# Sheet1.net
KiCad netlist of a schematic drawn in Altium Designer
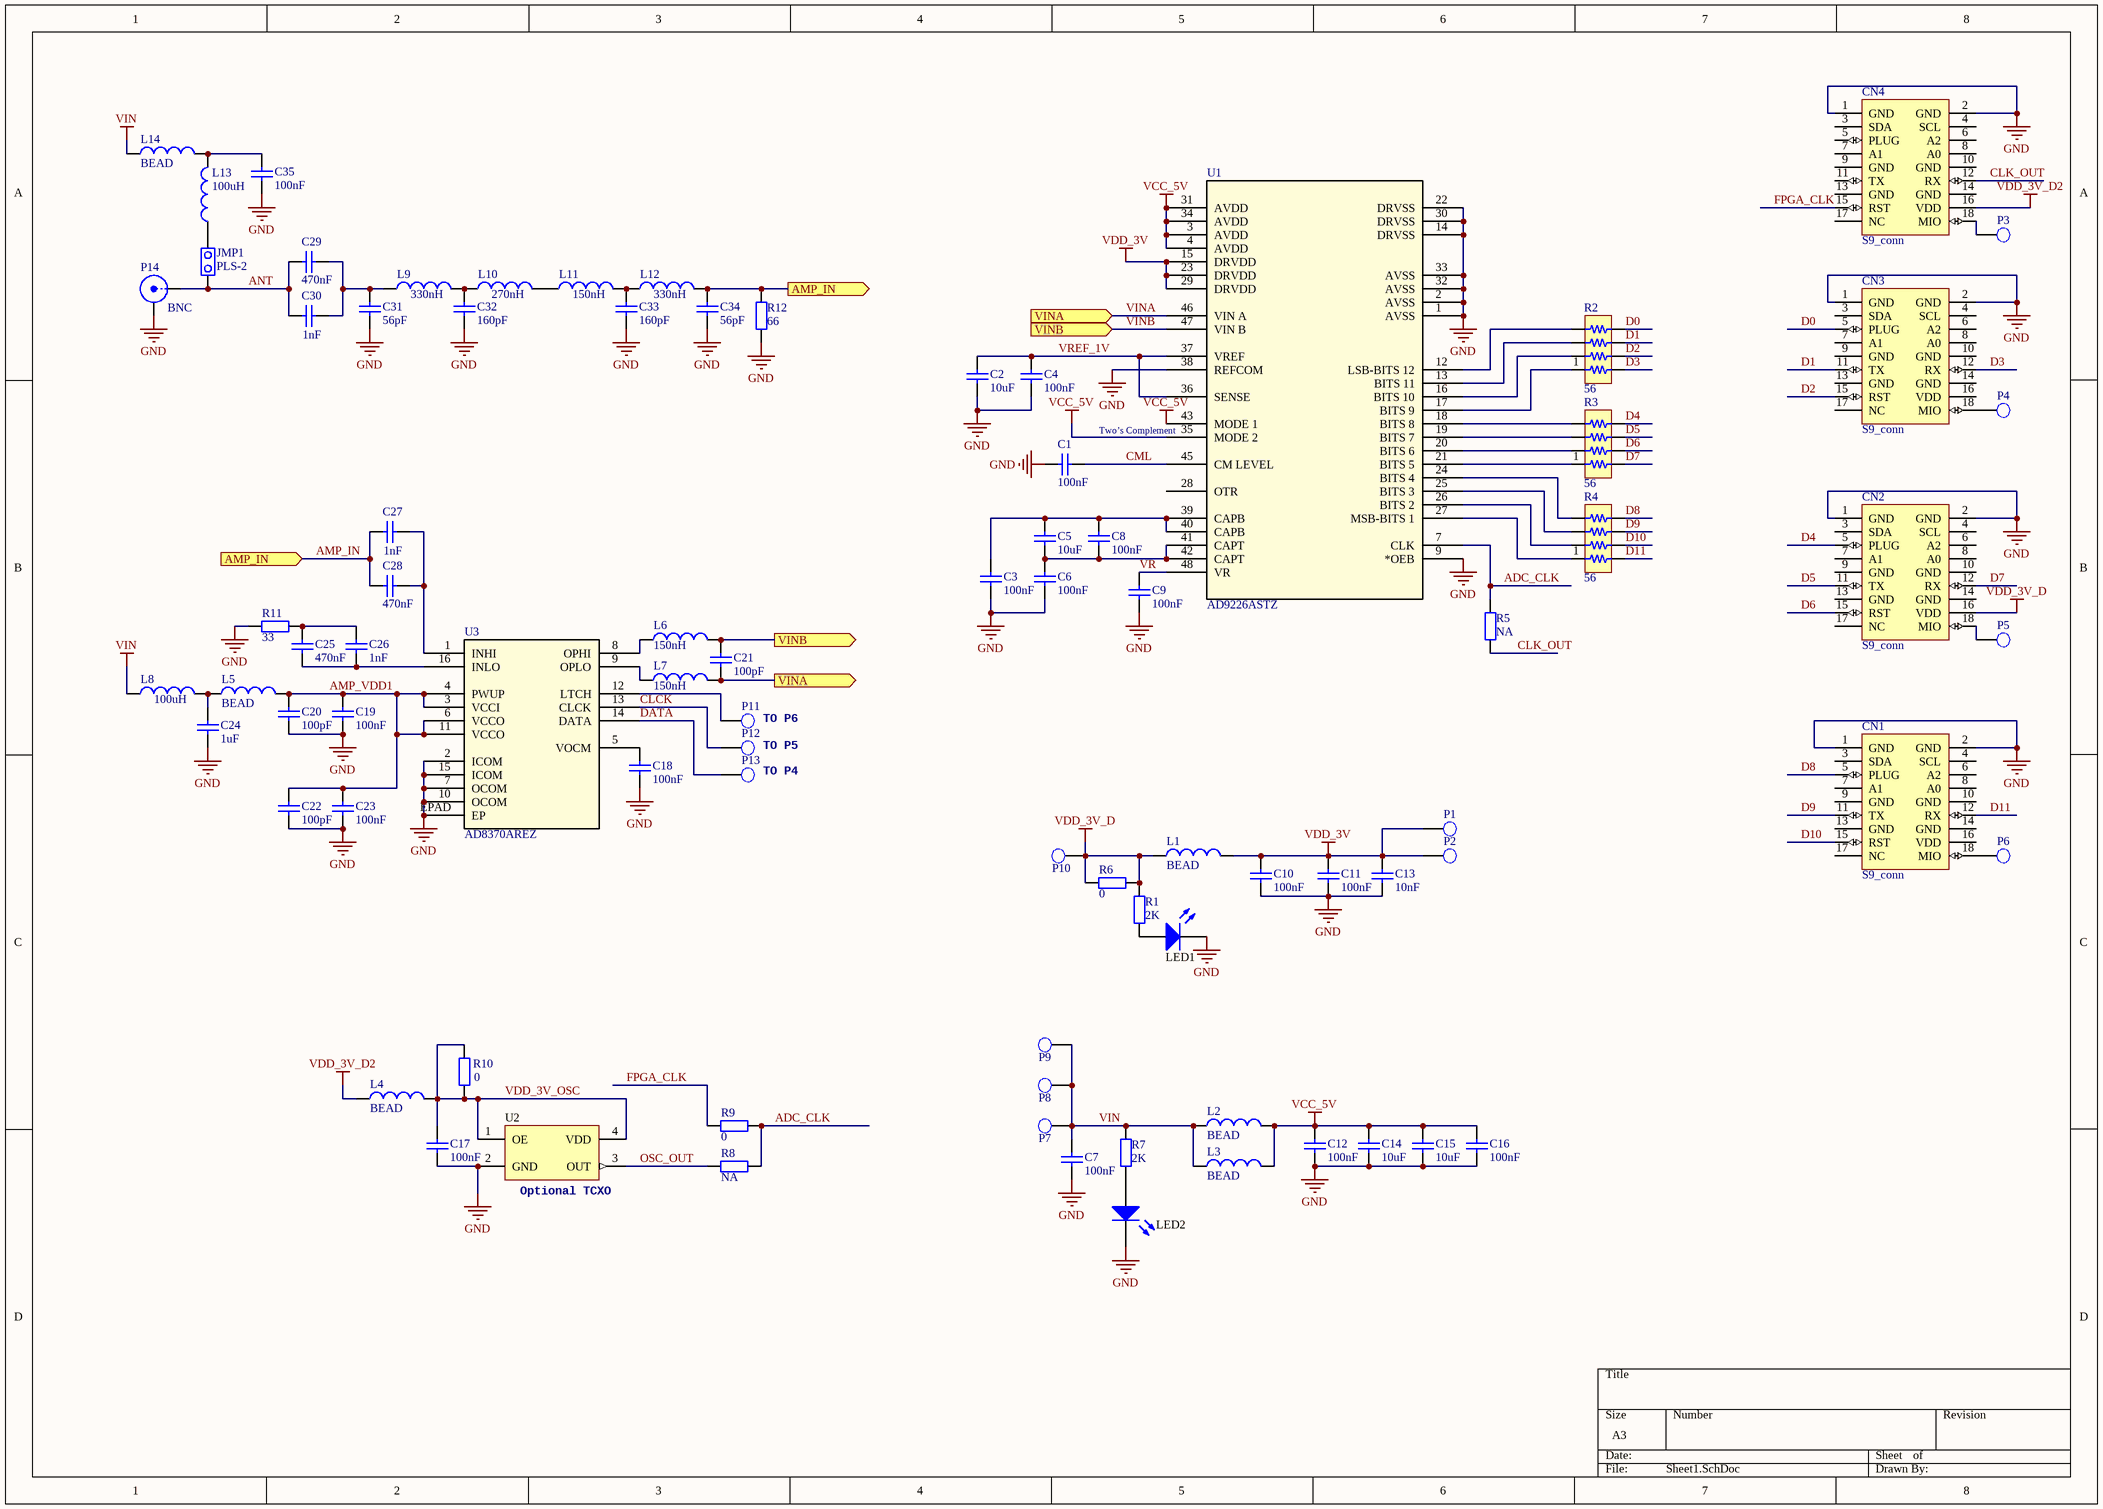
[diagram p0: Sheet1.SchDoc]

(export (version "E")
  (design (tool "Eeschema 10.0.6"))
  (components
    (comp (ref "C1")
      (value "100nF")
      (footprint "CAPC1608X90N")
      (description "Chip capacitor")
      (fields (field (name "VOLTAGE") "25V"))
      (libsource (lib "MyLibSch") (part "CC0805"))
    )
    (comp (ref "C2")
      (value "10uF")
      (footprint "CAPC1608X90N")
      (description "Chip capacitor")
      (fields (field (name "VOLTAGE") "25V"))
      (libsource (lib "MyLibSch") (part "CC0805"))
    )
    (comp (ref "C3")
      (value "100nF")
      (footprint "CAPC1608X90N")
      (description "Chip capacitor")
      (fields (field (name "VOLTAGE") "25V"))
      (libsource (lib "MyLibSch") (part "CC0805"))
    )
    (comp (ref "C4")
      (value "100nF")
      (footprint "CAPC1608X90N")
      (description "Chip capacitor")
      (fields (field (name "VOLTAGE") "25V"))
      (libsource (lib "MyLibSch") (part "CC0805"))
    )
    (comp (ref "C5")
      (value "10uF")
      (footprint "CAPC1608X90N")
      (description "Chip capacitor")
      (fields (field (name "VOLTAGE") "25V"))
      (libsource (lib "MyLibSch") (part "CC0805"))
    )
    (comp (ref "C6")
      (value "100nF")
      (footprint "CAPC1608X90N")
      (description "Chip capacitor")
      (fields (field (name "VOLTAGE") "25V"))
      (libsource (lib "MyLibSch") (part "CC0805"))
    )
    (comp (ref "C7")
      (value "100nF")
      (footprint "CAPC1608X90N")
      (description "Chip capacitor")
      (fields (field (name "VOLTAGE") "25V"))
      (libsource (lib "MyLibSch") (part "CC0805"))
    )
    (comp (ref "C8")
      (value "100nF")
      (footprint "CAPC1608X90N")
      (description "Chip capacitor")
      (fields (field (name "VOLTAGE") "25V"))
      (libsource (lib "MyLibSch") (part "CC0805"))
    )
    (comp (ref "C9")
      (value "100nF")
      (footprint "CAPC1608X90N")
      (description "Chip capacitor")
      (fields (field (name "VOLTAGE") "25V"))
      (libsource (lib "MyLibSch") (part "CC0805"))
    )
    (comp (ref "C10")
      (value "100nF")
      (footprint "CAPC1608X90N")
      (description "Chip capacitor")
      (fields (field (name "VOLTAGE") "25V"))
      (libsource (lib "MyLibSch") (part "CC0805"))
    )
    (comp (ref "C11")
      (value "100nF")
      (footprint "CAPC1608X90N")
      (description "Chip capacitor")
      (fields (field (name "VOLTAGE") "25V"))
      (libsource (lib "MyLibSch") (part "CC0805"))
    )
    (comp (ref "C12")
      (value "100nF")
      (footprint "CAPC1608X90N")
      (description "Chip capacitor")
      (fields (field (name "VOLTAGE") "25V"))
      (libsource (lib "MyLibSch") (part "CC0805"))
    )
    (comp (ref "C13")
      (value "10nF")
      (footprint "CAPC1608X90N")
      (description "Chip capacitor")
      (fields (field (name "VOLTAGE") "25V"))
      (libsource (lib "MyLibSch") (part "CC0805"))
    )
    (comp (ref "C14")
      (value "10uF")
      (footprint "CAPC1608X90N")
      (description "Chip capacitor")
      (fields (field (name "VOLTAGE") "25V"))
      (libsource (lib "MyLibSch") (part "CC0805"))
    )
    (comp (ref "C15")
      (value "10uF")
      (footprint "CAPC1608X90N")
      (description "Chip capacitor")
      (fields (field (name "VOLTAGE") "25V"))
      (libsource (lib "MyLibSch") (part "CC0805"))
    )
    (comp (ref "C16")
      (value "100nF")
      (footprint "CAPC1608X90N")
      (description "Chip capacitor")
      (fields (field (name "VOLTAGE") "25V"))
      (libsource (lib "MyLibSch") (part "CC0805"))
    )
    (comp (ref "C17")
      (value "100nF")
      (footprint "CAPC1608X90N")
      (description "Chip capacitor")
      (fields (field (name "VOLTAGE") "25V"))
      (libsource (lib "MyLibSch") (part "CC0805"))
    )
    (comp (ref "C18")
      (value "100nF")
      (footprint "CAPC2012X135N")
      (description "Chip capacitor")
      (fields (field (name "VOLTAGE") "25V"))
      (libsource (lib "MyLibSch") (part "CC0805"))
    )
    (comp (ref "C19")
      (value "100nF")
      (footprint "CAPC1608X90N")
      (description "Chip capacitor")
      (fields (field (name "VOLTAGE") "25V"))
      (libsource (lib "MyLibSch") (part "CC0805"))
    )
    (comp (ref "C20")
      (value "100pF")
      (footprint "CAPC1608X90N")
      (description "Chip capacitor")
      (fields (field (name "VOLTAGE") "25V"))
      (libsource (lib "MyLibSch") (part "CC0805"))
    )
    (comp (ref "C21")
      (value "100pF")
      (footprint "CAPC1608X90N")
      (description "Chip capacitor")
      (fields (field (name "VOLTAGE") "25V"))
      (libsource (lib "MyLibSch") (part "CC0805"))
    )
    (comp (ref "C22")
      (value "100pF")
      (footprint "CAPC1608X90N")
      (description "Chip capacitor")
      (fields (field (name "VOLTAGE") "25V"))
      (libsource (lib "MyLibSch") (part "CC0805"))
    )
    (comp (ref "C23")
      (value "100nF")
      (footprint "CAPC1608X90N")
      (description "Chip capacitor")
      (fields (field (name "VOLTAGE") "25V"))
      (libsource (lib "MyLibSch") (part "CC0805"))
    )
    (comp (ref "C24")
      (value "1uF")
      (footprint "CAPC1608X90N")
      (description "Chip capacitor")
      (fields (field (name "VOLTAGE") "25V"))
      (libsource (lib "MyLibSch") (part "CC0805"))
    )
    (comp (ref "C25")
      (value "470nF")
      (footprint "CAPC1608X90N")
      (description "Chip capacitor")
      (fields (field (name "VOLTAGE") "25V"))
      (libsource (lib "MyLibSch") (part "CC0805"))
    )
    (comp (ref "C26")
      (value "1nF")
      (footprint "CAPC1608X90N")
      (description "Chip capacitor")
      (fields (field (name "VOLTAGE") "25V"))
      (libsource (lib "MyLibSch") (part "CC0805"))
    )
    (comp (ref "C27")
      (value "1nF")
      (footprint "CAPC1608X90N")
      (description "Chip capacitor")
      (fields (field (name "VOLTAGE") "25V"))
      (libsource (lib "MyLibSch") (part "CC0805"))
    )
    (comp (ref "C28")
      (value "470nF")
      (footprint "CAPC1608X90N")
      (description "Chip capacitor")
      (fields (field (name "VOLTAGE") "25V"))
      (libsource (lib "MyLibSch") (part "CC0805"))
    )
    (comp (ref "C29")
      (value "470nF")
      (footprint "CAPC1608X90N")
      (description "Chip capacitor")
      (fields (field (name "VOLTAGE") "25V"))
      (libsource (lib "MyLibSch") (part "CC0805"))
    )
    (comp (ref "C30")
      (value "1nF")
      (footprint "CAPC1608X90N")
      (description "Chip capacitor")
      (fields (field (name "VOLTAGE") "25V"))
      (libsource (lib "MyLibSch") (part "CC0805"))
    )
    (comp (ref "C31")
      (value "56pF")
      (footprint "CAPC1608X90N")
      (description "Chip capacitor")
      (fields (field (name "VOLTAGE") "25V"))
      (libsource (lib "MyLibSch") (part "CC0805"))
    )
    (comp (ref "C32")
      (value "160pF")
      (footprint "CAPC1608X90N")
      (description "Chip capacitor")
      (fields (field (name "VOLTAGE") "25V"))
      (libsource (lib "MyLibSch") (part "CC0805"))
    )
    (comp (ref "C33")
      (value "160pF")
      (footprint "CAPC1608X90N")
      (description "Chip capacitor")
      (fields (field (name "VOLTAGE") "25V"))
      (libsource (lib "MyLibSch") (part "CC0805"))
    )
    (comp (ref "C34")
      (value "56pF")
      (footprint "CAPC1608X90N")
      (description "Chip capacitor")
      (fields (field (name "VOLTAGE") "25V"))
      (libsource (lib "MyLibSch") (part "CC0805"))
    )
    (comp (ref "C35")
      (value "100nF")
      (footprint "CAPC1608X90N")
      (description "Chip capacitor")
      (fields (field (name "VOLTAGE") "25V"))
      (libsource (lib "MyLibSch") (part "CC0805"))
    )
    (comp (ref "CN1") (value "S9_conn") (footprint "CONN9_2") (libsource (lib "lcd_lib") (part "S9_conn")))
    (comp (ref "CN2") (value "S9_conn") (footprint "CONN9_2") (libsource (lib "lcd_lib") (part "S9_conn")))
    (comp (ref "CN3") (value "S9_conn") (footprint "CONN9_2") (libsource (lib "lcd_lib") (part "S9_conn")))
    (comp (ref "CN4") (value "S9_conn") (footprint "CONN9_2") (libsource (lib "lcd_lib") (part "S9_conn")))
    (comp (ref "JMP1")
      (value "PLS-2")
      (footprint "HDR_1x2")
      (description "Jumper")
      (libsource (lib "MyLibConnectors") (part "JMP2"))
    )
    (comp (ref "L1")
      (value "BEAD")
      (footprint "INDC1608N")
      (description "Ferrit Bead")
      (libsource (lib "MyLibSch") (part "BEAD"))
    )
    (comp (ref "L2")
      (value "BEAD")
      (footprint "INDC1608N")
      (description "Ferrit Bead")
      (libsource (lib "MyLibSch") (part "BEAD"))
    )
    (comp (ref "L3")
      (value "BEAD")
      (footprint "INDC1608N")
      (description "Ferrit Bead")
      (libsource (lib "MyLibSch") (part "BEAD"))
    )
    (comp (ref "L4")
      (value "BEAD")
      (footprint "INDC1608N")
      (description "Ferrit Bead")
      (libsource (lib "MyLibSch") (part "BEAD"))
    )
    (comp (ref "L5")
      (value "BEAD")
      (footprint "INDC1608N")
      (description "Ferrit Bead")
      (libsource (lib "MyLibSch") (part "BEAD"))
    )
    (comp (ref "L6")
      (value "150nH")
      (footprint "RESC2012X70N")
      (description "Inductor")
      (fields (field (name "PUBLISHER") "Altium Limited"))
      (libsource (lib "Miscellaneous Devices") (part "Inductor"))
    )
    (comp (ref "L7")
      (value "150nH")
      (footprint "RESC2012X70N")
      (description "Inductor")
      (fields (field (name "PUBLISHER") "Altium Limited"))
      (libsource (lib "Miscellaneous Devices") (part "Inductor"))
    )
    (comp (ref "L8")
      (value "100uH")
      (footprint "INDC3216")
      (description "Inductor")
      (fields (field (name "PUBLISHER") "Altium Limited"))
      (libsource (lib "Miscellaneous Devices") (part "Inductor"))
    )
    (comp (ref "L9")
      (value "330nH")
      (footprint "MyLibPcb:V0805HD")
      (description "Inductor")
      (fields (field (name "PUBLISHER") "Altium Limited"))
      (libsource (lib "Miscellaneous Devices") (part "Inductor"))
    )
    (comp (ref "L10")
      (value "270nH")
      (footprint "MyLibPcb:V0805HD")
      (description "Inductor")
      (fields (field (name "PUBLISHER") "Altium Limited"))
      (libsource (lib "Miscellaneous Devices") (part "Inductor"))
    )
    (comp (ref "L11")
      (value "150nH")
      (footprint "MyLibPcb:V0805HD")
      (description "Inductor")
      (fields (field (name "PUBLISHER") "Altium Limited"))
      (libsource (lib "Miscellaneous Devices") (part "Inductor"))
    )
    (comp (ref "L12")
      (value "330nH")
      (footprint "MyLibPcb:V0805HD")
      (description "Inductor")
      (fields (field (name "PUBLISHER") "Altium Limited"))
      (libsource (lib "Miscellaneous Devices") (part "Inductor"))
    )
    (comp (ref "L13")
      (value "100uH")
      (footprint "INDC3216")
      (description "Inductor")
      (fields (field (name "PUBLISHER") "Altium Limited"))
      (libsource (lib "Miscellaneous Devices") (part "Inductor"))
    )
    (comp (ref "L14")
      (value "BEAD")
      (footprint "INDC1608N")
      (description "Ferrit Bead")
      (libsource (lib "MyLibSch") (part "BEAD"))
    )
    (comp (ref "LED1")
      (value "LED")
      (footprint "PcbLib3:LED_0603")
      (description "LED_0603")
      (libsource (lib "lcd_lib") (part "LED_0603"))
    )
    (comp (ref "LED2")
      (value "LED")
      (footprint "PcbLib3:LED_0603")
      (description "LED_0603")
      (libsource (lib "lcd_lib") (part "LED_0603"))
    )
    (comp (ref "P1")
      (value "Pad")
      (footprint "PcbLib3:Ext_pad_small2")
      (description "Pad for wire")
      (libsource (lib "lcd_lib") (part "Ext Pad"))
    )
    (comp (ref "P2")
      (value "Pad")
      (footprint "PcbLib3:Ext_pad_small2")
      (description "Pad for wire")
      (libsource (lib "lcd_lib") (part "Ext Pad"))
    )
    (comp (ref "P3")
      (value "Pad")
      (footprint "PcbLib3:Ext_pad_2")
      (description "Pad for wire")
      (libsource (lib "lcd_lib") (part "Ext Pad"))
    )
    (comp (ref "P4")
      (value "Pad")
      (footprint "PcbLib3:Ext_pad_2")
      (description "Pad for wire")
      (libsource (lib "lcd_lib") (part "Ext Pad"))
    )
    (comp (ref "P5")
      (value "Pad")
      (footprint "PcbLib3:Ext_pad_2")
      (description "Pad for wire")
      (libsource (lib "lcd_lib") (part "Ext Pad"))
    )
    (comp (ref "P6")
      (value "Pad")
      (footprint "PcbLib3:Ext_pad_2")
      (description "Pad for wire")
      (libsource (lib "lcd_lib") (part "Ext Pad"))
    )
    (comp (ref "P7")
      (value "Pad")
      (footprint "PcbLib3:Ext_pad_2")
      (description "Pad for wire")
      (libsource (lib "lcd_lib") (part "Ext Pad"))
    )
    (comp (ref "P8")
      (value "Pad")
      (footprint "Ext_hole")
      (description "Pad for wire")
      (libsource (lib "lcd_lib") (part "Ext Pad"))
    )
    (comp (ref "P9")
      (value "Pad")
      (footprint "Ext_hole")
      (description "Pad for wire")
      (libsource (lib "lcd_lib") (part "Ext Pad"))
    )
    (comp (ref "P10")
      (value "Pad")
      (footprint "PcbLib3:Ext_pad_small2")
      (description "Pad for wire")
      (libsource (lib "lcd_lib") (part "Ext Pad"))
    )
    (comp (ref "P11")
      (value "Pad")
      (footprint "PcbLib3:Ext_pad_small2")
      (description "Pad for wire")
      (libsource (lib "lcd_lib") (part "Ext Pad"))
    )
    (comp (ref "P12")
      (value "Pad")
      (footprint "PcbLib3:Ext_pad_small2")
      (description "Pad for wire")
      (libsource (lib "lcd_lib") (part "Ext Pad"))
    )
    (comp (ref "P13")
      (value "Pad")
      (footprint "PcbLib3:Ext_pad_small2")
      (description "Pad for wire")
      (libsource (lib "lcd_lib") (part "Ext Pad"))
    )
    (comp (ref "P14")
      (value "BNC")
      (footprint "BNC_RA CON")
      (description "BNC Elbow Connector")
      (fields (field (name "PUBLISHER") "Altium Limited"))
      (libsource (lib "Miscellaneous Connectors") (part "BNC"))
    )
    (comp (ref "R1")
      (value "2K")
      (footprint "RESC1608X55N")
      (description "Chip resistor")
      (fields (field (name "TOLERANCE") "5%"))
      (libsource (lib "MyLibSch") (part "RC0805"))
    )
    (comp (ref "R2")
      (value "56")
      (footprint "RESCAXS50P160X320X70-8N")
      (description "SMT Resistor Array")
      (libsource (lib "lcd_lib") (part "res_array_inv"))
    )
    (comp (ref "R3")
      (value "56")
      (footprint "RESCAXS50P160X320X70-8N")
      (description "SMT Resistor Array")
      (libsource (lib "lcd_lib") (part "res_array_inv"))
    )
    (comp (ref "R4")
      (value "56")
      (footprint "RESCAXS50P160X320X70-8N")
      (description "SMT Resistor Array")
      (libsource (lib "lcd_lib") (part "res_array_inv"))
    )
    (comp (ref "R5")
      (value "NA")
      (footprint "RESC1608X55N")
      (description "Chip resistor")
      (fields (field (name "TOLERANCE") "5%"))
      (libsource (lib "MyLibSch") (part "RC0805"))
    )
    (comp (ref "R6")
      (value "0")
      (footprint "RESC3216N_ZERO")
      (description "Chip resistor")
      (fields (field (name "TOLERANCE") "5%"))
      (libsource (lib "") (part "RC0805_1"))
    )
    (comp (ref "R7")
      (value "2K")
      (footprint "RESC1608X55N")
      (description "Chip resistor")
      (fields (field (name "TOLERANCE") "5%"))
      (libsource (lib "") (part "RC0805_2"))
    )
    (comp (ref "R8")
      (value "NA")
      (footprint "RESC1608X55N")
      (description "Chip resistor")
      (fields (field (name "TOLERANCE") "5%"))
      (libsource (lib "") (part "RC0805_1"))
    )
    (comp (ref "R9")
      (value "0")
      (footprint "RESC1608X55N")
      (description "Chip resistor")
      (fields (field (name "TOLERANCE") "5%"))
      (libsource (lib "") (part "RC0805_1"))
    )
    (comp (ref "R10")
      (value "0")
      (footprint "RESC3216N_ZERO")
      (description "Chip resistor")
      (fields (field (name "TOLERANCE") "5%"))
      (libsource (lib "MyLibSch") (part "RC0805"))
    )
    (comp (ref "R11")
      (value "33")
      (footprint "RESC1608X55N")
      (description "Chip resistor")
      (fields (field (name "TOLERANCE") "5%"))
      (libsource (lib "") (part "RC0805_1"))
    )
    (comp (ref "R12")
      (value "66")
      (footprint "RESC1608X55N")
      (description "Chip resistor")
      (fields (field (name "TOLERANCE") "5%"))
      (libsource (lib "MyLibSch") (part "RC0805"))
    )
    (comp (ref "U1")
      (value "AD9226ASTZ")
      (footprint "ST_48_ADI")
      (description "No Description Available")
      (libsource (lib "AD9226ASTZ") (part "AD9226ASTZ"))
    )
    (comp (ref "U2")
      (value "40MHz")
      (footprint "SX-6 QUARTZ")
      (description "Quartz Osc")
      (fields (field (name "Comment") "Quartz"))
      (libsource (lib "lcd_lib") (part "Quartz Osc"))
    )
    (comp (ref "U3")
      (value "AD8370AREZ")
      (footprint "RE_16_2_ADI")
      (description "No Description Available")
      (libsource (lib "AD8370AREZ") (part "AD8370AREZ"))
    )
  )
  (nets
    (net (code "1") (name "/ADC_CLK") (class "Default")
      (node (ref "R5") (pin "1") (pinfunction "1_1") (pintype "passive"))
      (node (ref "R8") (pin "1") (pinfunction "1_1") (pintype "passive"))
      (node (ref "R9") (pin "1") (pinfunction "1_1") (pintype "passive"))
      (node (ref "U1") (pin "7") (pinfunction "CLK_7") (pintype "passive"))
    )
    (net (code "2") (name "/AMP_IN") (class "Default")
      (node (ref "C27") (pin "2") (pinfunction "2_2") (pintype "passive"))
      (node (ref "C28") (pin "2") (pinfunction "2_2") (pintype "passive"))
      (node (ref "C34") (pin "2") (pinfunction "2_2") (pintype "passive"))
      (node (ref "L12") (pin "2") (pinfunction "2_2") (pintype "passive"))
      (node (ref "R12") (pin "1") (pinfunction "1_1") (pintype "passive"))
    )
    (net (code "3") (name "/AMP_VDD1") (class "Default")
      (node (ref "C19") (pin "2") (pinfunction "2_2") (pintype "passive"))
      (node (ref "C20") (pin "2") (pinfunction "2_2") (pintype "passive"))
      (node (ref "C22") (pin "2") (pinfunction "2_2") (pintype "passive"))
      (node (ref "C23") (pin "2") (pinfunction "2_2") (pintype "passive"))
      (node (ref "L5") (pin "2") (pinfunction "2_2") (pintype "passive"))
      (node (ref "U3") (pin "11") (pinfunction "VCCO_11") (pintype "power_in"))
      (node (ref "U3") (pin "3") (pinfunction "VCCI_3") (pintype "power_in"))
      (node (ref "U3") (pin "4") (pinfunction "PWUP_4") (pintype "passive"))
      (node (ref "U3") (pin "6") (pinfunction "VCCO_6") (pintype "power_in"))
    )
    (net (code "4") (name "/ANT") (class "Default")
      (node (ref "C29") (pin "2") (pinfunction "2_2") (pintype "passive"))
      (node (ref "C30") (pin "2") (pinfunction "2_2") (pintype "passive"))
      (node (ref "JMP1") (pin "1") (pinfunction "1_1") (pintype "passive"))
      (node (ref "P14") (pin "1") (pinfunction "X_1") (pintype "passive"))
    )
    (net (code "5") (name "/CLCK") (class "Default")
      (node (ref "P12") (pin "1") (pinfunction "Pad_1") (pintype "passive"))
      (node (ref "U3") (pin "13") (pinfunction "CLCK_13") (pintype "passive"))
    )
    (net (code "6") (name "/CLK_OUT") (class "Default")
      (node (ref "CN4") (pin "12") (pinfunction "RX_12") (pintype "bidirectional"))
      (node (ref "R5") (pin "2") (pinfunction "2_2") (pintype "passive"))
    )
    (net (code "7") (name "/CML") (class "Default")
      (node (ref "C1") (pin "2") (pinfunction "2_2") (pintype "passive"))
      (node (ref "U1") (pin "45") (pinfunction "CM_LEVEL_45") (pintype "passive"))
    )
    (net (code "8") (name "/D0") (class "Default")
      (node (ref "CN3") (pin "5") (pinfunction "PLUG_5") (pintype "bidirectional"))
      (node (ref "R2") (pin "5") (pinfunction "5_5") (pintype "passive"))
    )
    (net (code "9") (name "/D1") (class "Default")
      (node (ref "CN3") (pin "11") (pinfunction "TX_11") (pintype "bidirectional"))
      (node (ref "R2") (pin "6") (pinfunction "6_6") (pintype "passive"))
    )
    (net (code "10") (name "/D2") (class "Default")
      (node (ref "CN3") (pin "15") (pinfunction "RST_15") (pintype "bidirectional"))
      (node (ref "R2") (pin "7") (pinfunction "7_7") (pintype "passive"))
    )
    (net (code "11") (name "/D3") (class "Default")
      (node (ref "CN3") (pin "12") (pinfunction "RX_12") (pintype "bidirectional"))
      (node (ref "R2") (pin "8") (pinfunction "8_8") (pintype "passive"))
    )
    (net (code "12") (name "/D4") (class "Default")
      (node (ref "CN2") (pin "5") (pinfunction "PLUG_5") (pintype "bidirectional"))
      (node (ref "R3") (pin "5") (pinfunction "5_5") (pintype "passive"))
    )
    (net (code "13") (name "/D5") (class "Default")
      (node (ref "CN2") (pin "11") (pinfunction "TX_11") (pintype "bidirectional"))
      (node (ref "R3") (pin "6") (pinfunction "6_6") (pintype "passive"))
    )
    (net (code "14") (name "/D6") (class "Default")
      (node (ref "CN2") (pin "15") (pinfunction "RST_15") (pintype "bidirectional"))
      (node (ref "R3") (pin "7") (pinfunction "7_7") (pintype "passive"))
    )
    (net (code "15") (name "/D7") (class "Default")
      (node (ref "CN2") (pin "12") (pinfunction "RX_12") (pintype "bidirectional"))
      (node (ref "R3") (pin "8") (pinfunction "8_8") (pintype "passive"))
    )
    (net (code "16") (name "/D8") (class "Default")
      (node (ref "CN1") (pin "5") (pinfunction "PLUG_5") (pintype "bidirectional"))
      (node (ref "R4") (pin "5") (pinfunction "5_5") (pintype "passive"))
    )
    (net (code "17") (name "/D9") (class "Default")
      (node (ref "CN1") (pin "11") (pinfunction "TX_11") (pintype "bidirectional"))
      (node (ref "R4") (pin "6") (pinfunction "6_6") (pintype "passive"))
    )
    (net (code "18") (name "/D10") (class "Default")
      (node (ref "CN1") (pin "15") (pinfunction "RST_15") (pintype "bidirectional"))
      (node (ref "R4") (pin "7") (pinfunction "7_7") (pintype "passive"))
    )
    (net (code "19") (name "/D11") (class "Default")
      (node (ref "CN1") (pin "12") (pinfunction "RX_12") (pintype "bidirectional"))
      (node (ref "R4") (pin "8") (pinfunction "8_8") (pintype "passive"))
    )
    (net (code "20") (name "/DATA") (class "Default")
      (node (ref "P13") (pin "1") (pinfunction "Pad_1") (pintype "passive"))
      (node (ref "U3") (pin "14") (pinfunction "DATA_14") (pintype "passive"))
    )
    (net (code "21") (name "/FPGA_CLK") (class "Default")
      (node (ref "CN4") (pin "15") (pinfunction "RST_15") (pintype "bidirectional"))
      (node (ref "R9") (pin "2") (pinfunction "2_2") (pintype "passive"))
    )
    (net (code "22") (name "/OSC_OUT") (class "Default")
      (node (ref "R8") (pin "2") (pinfunction "2_2") (pintype "passive"))
      (node (ref "U2") (pin "3") (pinfunction "OUT_3") (pintype "output"))
    )
    (net (code "23") (name "/VDD_3V_OSC") (class "Default")
      (node (ref "C17") (pin "2") (pinfunction "2_2") (pintype "passive"))
      (node (ref "L4") (pin "2") (pinfunction "2_2") (pintype "passive"))
      (node (ref "R10") (pin "1") (pinfunction "1_1") (pintype "passive"))
      (node (ref "R10") (pin "2") (pinfunction "2_2") (pintype "passive"))
      (node (ref "U2") (pin "1") (pinfunction "OE_1") (pintype "passive"))
      (node (ref "U2") (pin "4") (pinfunction "VDD_4") (pintype "power_in"))
    )
    (net (code "24") (name "/VINA") (class "Default")
      (node (ref "C21") (pin "1") (pinfunction "1_1") (pintype "passive"))
      (node (ref "L7") (pin "2") (pinfunction "2_2") (pintype "passive"))
      (node (ref "U1") (pin "46") (pinfunction "VIN_A_46") (pintype "passive"))
    )
    (net (code "25") (name "/VINB") (class "Default")
      (node (ref "C21") (pin "2") (pinfunction "2_2") (pintype "passive"))
      (node (ref "L6") (pin "2") (pinfunction "2_2") (pintype "passive"))
      (node (ref "U1") (pin "47") (pinfunction "VIN_B_47") (pintype "passive"))
    )
    (net (code "26") (name "/VR") (class "Default")
      (node (ref "C9") (pin "2") (pinfunction "2_2") (pintype "passive"))
      (node (ref "U1") (pin "48") (pinfunction "VR_48") (pintype "passive"))
    )
    (net (code "27") (name "/VREF_1V") (class "Default")
      (node (ref "C2") (pin "2") (pinfunction "2_2") (pintype "passive"))
      (node (ref "C4") (pin "2") (pinfunction "2_2") (pintype "passive"))
      (node (ref "U1") (pin "36") (pinfunction "SENSE_36") (pintype "passive"))
      (node (ref "U1") (pin "37") (pinfunction "VREF_37") (pintype "passive"))
    )
    (net (code "28") (name "GND") (class "Default")
      (node (ref "C1") (pin "1") (pinfunction "1_1") (pintype "passive"))
      (node (ref "C10") (pin "1") (pinfunction "1_1") (pintype "passive"))
      (node (ref "C11") (pin "1") (pinfunction "1_1") (pintype "passive"))
      (node (ref "C12") (pin "1") (pinfunction "1_1") (pintype "passive"))
      (node (ref "C13") (pin "1") (pinfunction "1_1") (pintype "passive"))
      (node (ref "C14") (pin "1") (pinfunction "1_1") (pintype "passive"))
      (node (ref "C15") (pin "1") (pinfunction "1_1") (pintype "passive"))
      (node (ref "C16") (pin "1") (pinfunction "1_1") (pintype "passive"))
      (node (ref "C17") (pin "1") (pinfunction "1_1") (pintype "passive"))
      (node (ref "C18") (pin "1") (pinfunction "1_1") (pintype "passive"))
      (node (ref "C19") (pin "1") (pinfunction "1_1") (pintype "passive"))
      (node (ref "C2") (pin "1") (pinfunction "1_1") (pintype "passive"))
      (node (ref "C20") (pin "1") (pinfunction "1_1") (pintype "passive"))
      (node (ref "C22") (pin "1") (pinfunction "1_1") (pintype "passive"))
      (node (ref "C23") (pin "1") (pinfunction "1_1") (pintype "passive"))
      (node (ref "C24") (pin "1") (pinfunction "1_1") (pintype "passive"))
      (node (ref "C3") (pin "1") (pinfunction "1_1") (pintype "passive"))
      (node (ref "C31") (pin "1") (pinfunction "1_1") (pintype "passive"))
      (node (ref "C32") (pin "1") (pinfunction "1_1") (pintype "passive"))
      (node (ref "C33") (pin "1") (pinfunction "1_1") (pintype "passive"))
      (node (ref "C34") (pin "1") (pinfunction "1_1") (pintype "passive"))
      (node (ref "C35") (pin "1") (pinfunction "1_1") (pintype "passive"))
      (node (ref "C4") (pin "1") (pinfunction "1_1") (pintype "passive"))
      (node (ref "C6") (pin "1") (pinfunction "1_1") (pintype "passive"))
      (node (ref "C7") (pin "1") (pinfunction "1_1") (pintype "passive"))
      (node (ref "C9") (pin "1") (pinfunction "1_1") (pintype "passive"))
      (node (ref "CN1") (pin "1") (pinfunction "GND_1") (pintype "passive"))
      (node (ref "CN1") (pin "2") (pinfunction "GND_2") (pintype "passive"))
      (node (ref "CN2") (pin "1") (pinfunction "GND_1") (pintype "passive"))
      (node (ref "CN2") (pin "2") (pinfunction "GND_2") (pintype "passive"))
      (node (ref "CN3") (pin "1") (pinfunction "GND_1") (pintype "passive"))
      (node (ref "CN3") (pin "2") (pinfunction "GND_2") (pintype "passive"))
      (node (ref "CN4") (pin "1") (pinfunction "GND_1") (pintype "passive"))
      (node (ref "CN4") (pin "2") (pinfunction "GND_2") (pintype "passive"))
      (node (ref "LED1") (pin "2") (pinfunction "K_2") (pintype "passive"))
      (node (ref "LED2") (pin "2") (pinfunction "K_2") (pintype "passive"))
      (node (ref "P14") (pin "2") (pinfunction "Y_2") (pintype "passive"))
      (node (ref "R11") (pin "2") (pinfunction "2_2") (pintype "passive"))
      (node (ref "R12") (pin "2") (pinfunction "2_2") (pintype "passive"))
      (node (ref "U1") (pin "1") (pinfunction "AVSS_1") (pintype "passive"))
      (node (ref "U1") (pin "14") (pinfunction "DRVSS_14") (pintype "passive"))
      (node (ref "U1") (pin "2") (pinfunction "AVSS_2") (pintype "passive"))
      (node (ref "U1") (pin "22") (pinfunction "DRVSS_22") (pintype "passive"))
      (node (ref "U1") (pin "30") (pinfunction "DRVSS_30") (pintype "passive"))
      (node (ref "U1") (pin "32") (pinfunction "AVSS_32") (pintype "passive"))
      (node (ref "U1") (pin "33") (pinfunction "AVSS_33") (pintype "passive"))
      (node (ref "U1") (pin "38") (pinfunction "REFCOM_38") (pintype "passive"))
      (node (ref "U1") (pin "9") (pinfunction "*OEB_9") (pintype "passive"))
      (node (ref "U2") (pin "2") (pinfunction "GND_2") (pintype "power_in"))
      (node (ref "U3") (pin "10") (pinfunction "OCOM_10") (pintype "passive"))
      (node (ref "U3") (pin "15") (pinfunction "ICOM_15") (pintype "passive"))
      (node (ref "U3") (pin "2") (pinfunction "ICOM_2") (pintype "passive"))
      (node (ref "U3") (pin "7") (pinfunction "OCOM_7") (pintype "passive"))
      (node (ref "U3") (pin "EPAD") (pinfunction "EP_EPAD") (pintype "passive"))
    )
    (net (code "29") (name "Net-(C3-Pad2)") (class "Default")
      (node (ref "C3") (pin "2") (pinfunction "2_2") (pintype "passive"))
      (node (ref "C5") (pin "2") (pinfunction "2_2") (pintype "passive"))
      (node (ref "C8") (pin "2") (pinfunction "2_2") (pintype "passive"))
      (node (ref "U1") (pin "39") (pinfunction "CAPB_39") (pintype "passive"))
      (node (ref "U1") (pin "40") (pinfunction "CAPB_40") (pintype "passive"))
    )
    (net (code "30") (name "Net-(C5-Pad1)") (class "Default")
      (node (ref "C5") (pin "1") (pinfunction "1_1") (pintype "passive"))
      (node (ref "C6") (pin "2") (pinfunction "2_2") (pintype "passive"))
      (node (ref "C8") (pin "1") (pinfunction "1_1") (pintype "passive"))
      (node (ref "U1") (pin "41") (pinfunction "CAPT_41") (pintype "passive"))
      (node (ref "U1") (pin "42") (pinfunction "CAPT_42") (pintype "passive"))
    )
    (net (code "31") (name "Net-(C24-Pad2)") (class "Default")
      (node (ref "C24") (pin "2") (pinfunction "2_2") (pintype "passive"))
      (node (ref "L5") (pin "1") (pinfunction "1_1") (pintype "passive"))
      (node (ref "L8") (pin "2") (pinfunction "2_2") (pintype "passive"))
    )
    (net (code "32") (name "Net-(C25-Pad2)") (class "Default")
      (node (ref "C25") (pin "2") (pinfunction "2_2") (pintype "passive"))
      (node (ref "C26") (pin "2") (pinfunction "2_2") (pintype "passive"))
      (node (ref "R11") (pin "1") (pinfunction "1_1") (pintype "passive"))
    )
    (net (code "33") (name "Net-(C29-Pad1)") (class "Default")
      (node (ref "C29") (pin "1") (pinfunction "1_1") (pintype "passive"))
      (node (ref "C30") (pin "1") (pinfunction "1_1") (pintype "passive"))
      (node (ref "C31") (pin "2") (pinfunction "2_2") (pintype "passive"))
      (node (ref "L9") (pin "1") (pinfunction "1_1") (pintype "passive"))
    )
    (net (code "34") (name "Net-(C32-Pad2)") (class "Default")
      (node (ref "C32") (pin "2") (pinfunction "2_2") (pintype "passive"))
      (node (ref "L10") (pin "1") (pinfunction "1_1") (pintype "passive"))
      (node (ref "L9") (pin "2") (pinfunction "2_2") (pintype "passive"))
    )
    (net (code "35") (name "Net-(C33-Pad2)") (class "Default")
      (node (ref "C33") (pin "2") (pinfunction "2_2") (pintype "passive"))
      (node (ref "L11") (pin "2") (pinfunction "2_2") (pintype "passive"))
      (node (ref "L12") (pin "1") (pinfunction "1_1") (pintype "passive"))
    )
    (net (code "36") (name "Net-(C35-Pad2)") (class "Default")
      (node (ref "C35") (pin "2") (pinfunction "2_2") (pintype "passive"))
      (node (ref "L13") (pin "2") (pinfunction "2_2") (pintype "passive"))
      (node (ref "L14") (pin "2") (pinfunction "2_2") (pintype "passive"))
    )
    (net (code "37") (name "Net-(CN1-MIO)") (class "Default")
      (node (ref "CN1") (pin "18") (pinfunction "MIO_18") (pintype "bidirectional"))
      (node (ref "P6") (pin "1") (pinfunction "Pad_1") (pintype "passive"))
    )
    (net (code "38") (name "Net-(CN2-MIO)") (class "Default")
      (node (ref "CN2") (pin "18") (pinfunction "MIO_18") (pintype "bidirectional"))
      (node (ref "P5") (pin "1") (pinfunction "Pad_1") (pintype "passive"))
    )
    (net (code "39") (name "Net-(CN3-MIO)") (class "Default")
      (node (ref "CN3") (pin "18") (pinfunction "MIO_18") (pintype "bidirectional"))
      (node (ref "P4") (pin "1") (pinfunction "Pad_1") (pintype "passive"))
    )
    (net (code "40") (name "Net-(CN4-MIO)") (class "Default")
      (node (ref "CN4") (pin "18") (pinfunction "MIO_18") (pintype "bidirectional"))
      (node (ref "P3") (pin "1") (pinfunction "Pad_1") (pintype "passive"))
    )
    (net (code "41") (name "Net-(JMP1-Pad2)") (class "Default")
      (node (ref "JMP1") (pin "2") (pinfunction "2_2") (pintype "passive"))
      (node (ref "L13") (pin "1") (pinfunction "1_1") (pintype "passive"))
    )
    (net (code "42") (name "Net-(L10-Pad2)") (class "Default")
      (node (ref "L10") (pin "2") (pinfunction "2_2") (pintype "passive"))
      (node (ref "L11") (pin "1") (pinfunction "1_1") (pintype "passive"))
    )
    (net (code "43") (name "Net-(LED1-A)") (class "Default")
      (node (ref "LED1") (pin "1") (pinfunction "A_1") (pintype "passive"))
      (node (ref "R1") (pin "2") (pinfunction "2_2") (pintype "passive"))
    )
    (net (code "44") (name "Net-(LED2-A)") (class "Default")
      (node (ref "LED2") (pin "1") (pinfunction "A_1") (pintype "passive"))
      (node (ref "R7") (pin "1") (pinfunction "1_1") (pintype "passive"))
    )
    (net (code "45") (name "Net-(U1-BITS_2)") (class "Default")
      (node (ref "R4") (pin "2") (pinfunction "2_2") (pintype "passive"))
      (node (ref "U1") (pin "26") (pinfunction "BITS_2_26") (pintype "passive"))
    )
    (net (code "46") (name "Net-(U1-BITS_3)") (class "Default")
      (node (ref "R4") (pin "3") (pinfunction "3_3") (pintype "passive"))
      (node (ref "U1") (pin "25") (pinfunction "BITS_3_25") (pintype "passive"))
    )
    (net (code "47") (name "Net-(U1-BITS_4)") (class "Default")
      (node (ref "R4") (pin "4") (pinfunction "4_4") (pintype "passive"))
      (node (ref "U1") (pin "24") (pinfunction "BITS_4_24") (pintype "passive"))
    )
    (net (code "48") (name "Net-(U1-BITS_5)") (class "Default")
      (node (ref "R3") (pin "1") (pinfunction "1_1") (pintype "passive"))
      (node (ref "U1") (pin "21") (pinfunction "BITS_5_21") (pintype "passive"))
    )
    (net (code "49") (name "Net-(U1-BITS_6)") (class "Default")
      (node (ref "R3") (pin "2") (pinfunction "2_2") (pintype "passive"))
      (node (ref "U1") (pin "20") (pinfunction "BITS_6_20") (pintype "passive"))
    )
    (net (code "50") (name "Net-(U1-BITS_7)") (class "Default")
      (node (ref "R3") (pin "3") (pinfunction "3_3") (pintype "passive"))
      (node (ref "U1") (pin "19") (pinfunction "BITS_7_19") (pintype "passive"))
    )
    (net (code "51") (name "Net-(U1-BITS_8)") (class "Default")
      (node (ref "R3") (pin "4") (pinfunction "4_4") (pintype "passive"))
      (node (ref "U1") (pin "18") (pinfunction "BITS_8_18") (pintype "passive"))
    )
    (net (code "52") (name "Net-(U1-BITS_9)") (class "Default")
      (node (ref "R2") (pin "1") (pinfunction "1_1") (pintype "passive"))
      (node (ref "U1") (pin "17") (pinfunction "BITS_9_17") (pintype "passive"))
    )
    (net (code "53") (name "Net-(U1-BITS_10)") (class "Default")
      (node (ref "R2") (pin "2") (pinfunction "2_2") (pintype "passive"))
      (node (ref "U1") (pin "16") (pinfunction "BITS_10_16") (pintype "passive"))
    )
    (net (code "54") (name "Net-(U1-BITS_11)") (class "Default")
      (node (ref "R2") (pin "3") (pinfunction "3_3") (pintype "passive"))
      (node (ref "U1") (pin "13") (pinfunction "BITS_11_13") (pintype "passive"))
    )
    (net (code "55") (name "Net-(U1-LSB-BITS_12)") (class "Default")
      (node (ref "R2") (pin "4") (pinfunction "4_4") (pintype "passive"))
      (node (ref "U1") (pin "12") (pinfunction "LSB-BITS_12_12") (pintype "passive"))
    )
    (net (code "56") (name "Net-(U1-MSB-BITS_1)") (class "Default")
      (node (ref "R4") (pin "1") (pinfunction "1_1") (pintype "passive"))
      (node (ref "U1") (pin "27") (pinfunction "MSB-BITS_1_27") (pintype "passive"))
    )
    (net (code "57") (name "Net-(U3-INHI)") (class "Default")
      (node (ref "C27") (pin "1") (pinfunction "1_1") (pintype "passive"))
      (node (ref "C28") (pin "1") (pinfunction "1_1") (pintype "passive"))
      (node (ref "U3") (pin "1") (pinfunction "INHI_1") (pintype "passive"))
    )
    (net (code "58") (name "Net-(U3-INLO)") (class "Default")
      (node (ref "C25") (pin "1") (pinfunction "1_1") (pintype "passive"))
      (node (ref "C26") (pin "1") (pinfunction "1_1") (pintype "passive"))
      (node (ref "U3") (pin "16") (pinfunction "INLO_16") (pintype "passive"))
    )
    (net (code "59") (name "Net-(U3-LTCH)") (class "Default")
      (node (ref "P11") (pin "1") (pinfunction "Pad_1") (pintype "passive"))
      (node (ref "U3") (pin "12") (pinfunction "LTCH_12") (pintype "passive"))
    )
    (net (code "60") (name "Net-(U3-OPHI)") (class "Default")
      (node (ref "L6") (pin "1") (pinfunction "1_1") (pintype "passive"))
      (node (ref "U3") (pin "8") (pinfunction "OPHI_8") (pintype "passive"))
    )
    (net (code "61") (name "Net-(U3-OPLO)") (class "Default")
      (node (ref "L7") (pin "1") (pinfunction "1_1") (pintype "passive"))
      (node (ref "U3") (pin "9") (pinfunction "OPLO_9") (pintype "passive"))
    )
    (net (code "62") (name "Net-(U3-VOCM)") (class "Default")
      (node (ref "C18") (pin "2") (pinfunction "2_2") (pintype "passive"))
      (node (ref "U3") (pin "5") (pinfunction "VOCM_5") (pintype "passive"))
    )
    (net (code "63") (name "VCC_5V") (class "Default")
      (node (ref "C12") (pin "2") (pinfunction "2_2") (pintype "passive"))
      (node (ref "C14") (pin "2") (pinfunction "2_2") (pintype "passive"))
      (node (ref "C15") (pin "2") (pinfunction "2_2") (pintype "passive"))
      (node (ref "C16") (pin "2") (pinfunction "2_2") (pintype "passive"))
      (node (ref "L2") (pin "2") (pinfunction "2_2") (pintype "passive"))
      (node (ref "L3") (pin "2") (pinfunction "2_2") (pintype "passive"))
      (node (ref "U1") (pin "3") (pinfunction "AVDD_3") (pintype "passive"))
      (node (ref "U1") (pin "31") (pinfunction "AVDD_31") (pintype "passive"))
      (node (ref "U1") (pin "34") (pinfunction "AVDD_34") (pintype "passive"))
      (node (ref "U1") (pin "35") (pinfunction "MODE_2_35") (pintype "passive"))
      (node (ref "U1") (pin "4") (pinfunction "AVDD_4") (pintype "passive"))
      (node (ref "U1") (pin "43") (pinfunction "MODE_1_43") (pintype "passive"))
    )
    (net (code "64") (name "VDD_3V") (class "Default")
      (node (ref "C10") (pin "2") (pinfunction "2_2") (pintype "passive"))
      (node (ref "C11") (pin "2") (pinfunction "2_2") (pintype "passive"))
      (node (ref "C13") (pin "2") (pinfunction "2_2") (pintype "passive"))
      (node (ref "L1") (pin "2") (pinfunction "2_2") (pintype "passive"))
      (node (ref "P1") (pin "1") (pinfunction "Pad_1") (pintype "passive"))
      (node (ref "P2") (pin "1") (pinfunction "Pad_1") (pintype "passive"))
      (node (ref "U1") (pin "15") (pinfunction "DRVDD_15") (pintype "passive"))
      (node (ref "U1") (pin "23") (pinfunction "DRVDD_23") (pintype "passive"))
      (node (ref "U1") (pin "29") (pinfunction "DRVDD_29") (pintype "passive"))
    )
    (net (code "65") (name "VDD_3V_D") (class "Default")
      (node (ref "CN2") (pin "16") (pinfunction "VDD_16") (pintype "passive"))
      (node (ref "L1") (pin "1") (pinfunction "1_1") (pintype "passive"))
      (node (ref "P10") (pin "1") (pinfunction "Pad_1") (pintype "passive"))
      (node (ref "R1") (pin "1") (pinfunction "1_1") (pintype "passive"))
      (node (ref "R6") (pin "1") (pinfunction "1_1") (pintype "passive"))
      (node (ref "R6") (pin "2") (pinfunction "2_2") (pintype "passive"))
    )
    (net (code "66") (name "VDD_3V_D2") (class "Default")
      (node (ref "CN4") (pin "16") (pinfunction "VDD_16") (pintype "passive"))
      (node (ref "L4") (pin "1") (pinfunction "1_1") (pintype "passive"))
    )
    (net (code "67") (name "VIN") (class "Default")
      (node (ref "C7") (pin "2") (pinfunction "2_2") (pintype "passive"))
      (node (ref "L14") (pin "1") (pinfunction "1_1") (pintype "passive"))
      (node (ref "L2") (pin "1") (pinfunction "1_1") (pintype "passive"))
      (node (ref "L3") (pin "1") (pinfunction "1_1") (pintype "passive"))
      (node (ref "L8") (pin "1") (pinfunction "1_1") (pintype "passive"))
      (node (ref "P7") (pin "1") (pinfunction "Pad_1") (pintype "passive"))
      (node (ref "P8") (pin "1") (pinfunction "Pad_1") (pintype "passive"))
      (node (ref "P9") (pin "1") (pinfunction "Pad_1") (pintype "passive"))
      (node (ref "R7") (pin "2") (pinfunction "2_2") (pintype "passive"))
    )
    (net (code "68") (name "unconnected-(CN1-A0-Pad8)") (class "Default")
      (node (ref "CN1") (pin "8") (pinfunction "A0_8") (pintype "passive"))
    )
    (net (code "69") (name "unconnected-(CN1-A1-Pad7)") (class "Default")
      (node (ref "CN1") (pin "7") (pinfunction "A1_7") (pintype "passive"))
    )
    (net (code "70") (name "unconnected-(CN1-A2-Pad6)") (class "Default")
      (node (ref "CN1") (pin "6") (pinfunction "A2_6") (pintype "passive"))
    )
    (net (code "71") (name "unconnected-(CN1-GND-Pad9)") (class "Default")
      (node (ref "CN1") (pin "9") (pinfunction "GND_9") (pintype "passive"))
    )
    (net (code "72") (name "unconnected-(CN1-GND-Pad10)") (class "Default")
      (node (ref "CN1") (pin "10") (pinfunction "GND_10") (pintype "passive"))
    )
    (net (code "73") (name "unconnected-(CN1-GND-Pad13)") (class "Default")
      (node (ref "CN1") (pin "13") (pinfunction "GND_13") (pintype "passive"))
    )
    (net (code "74") (name "unconnected-(CN1-GND-Pad14)") (class "Default")
      (node (ref "CN1") (pin "14") (pinfunction "GND_14") (pintype "passive"))
    )
    (net (code "75") (name "unconnected-(CN1-NC-Pad17)") (class "Default")
      (node (ref "CN1") (pin "17") (pinfunction "NC_17") (pintype "passive"))
    )
    (net (code "76") (name "unconnected-(CN1-SCL-Pad4)") (class "Default")
      (node (ref "CN1") (pin "4") (pinfunction "SCL_4") (pintype "passive"))
    )
    (net (code "77") (name "unconnected-(CN1-SDA-Pad3)") (class "Default")
      (node (ref "CN1") (pin "3") (pinfunction "SDA_3") (pintype "passive"))
    )
    (net (code "78") (name "unconnected-(CN1-VDD-Pad16)") (class "Default")
      (node (ref "CN1") (pin "16") (pinfunction "VDD_16") (pintype "passive"))
    )
    (net (code "79") (name "unconnected-(CN2-A0-Pad8)") (class "Default")
      (node (ref "CN2") (pin "8") (pinfunction "A0_8") (pintype "passive"))
    )
    (net (code "80") (name "unconnected-(CN2-A1-Pad7)") (class "Default")
      (node (ref "CN2") (pin "7") (pinfunction "A1_7") (pintype "passive"))
    )
    (net (code "81") (name "unconnected-(CN2-A2-Pad6)") (class "Default")
      (node (ref "CN2") (pin "6") (pinfunction "A2_6") (pintype "passive"))
    )
    (net (code "82") (name "unconnected-(CN2-GND-Pad9)") (class "Default")
      (node (ref "CN2") (pin "9") (pinfunction "GND_9") (pintype "passive"))
    )
    (net (code "83") (name "unconnected-(CN2-GND-Pad10)") (class "Default")
      (node (ref "CN2") (pin "10") (pinfunction "GND_10") (pintype "passive"))
    )
    (net (code "84") (name "unconnected-(CN2-GND-Pad13)") (class "Default")
      (node (ref "CN2") (pin "13") (pinfunction "GND_13") (pintype "passive"))
    )
    (net (code "85") (name "unconnected-(CN2-GND-Pad14)") (class "Default")
      (node (ref "CN2") (pin "14") (pinfunction "GND_14") (pintype "passive"))
    )
    (net (code "86") (name "unconnected-(CN2-NC-Pad17)") (class "Default")
      (node (ref "CN2") (pin "17") (pinfunction "NC_17") (pintype "passive"))
    )
    (net (code "87") (name "unconnected-(CN2-SCL-Pad4)") (class "Default")
      (node (ref "CN2") (pin "4") (pinfunction "SCL_4") (pintype "passive"))
    )
    (net (code "88") (name "unconnected-(CN2-SDA-Pad3)") (class "Default")
      (node (ref "CN2") (pin "3") (pinfunction "SDA_3") (pintype "passive"))
    )
    (net (code "89") (name "unconnected-(CN3-A0-Pad8)") (class "Default")
      (node (ref "CN3") (pin "8") (pinfunction "A0_8") (pintype "passive"))
    )
    (net (code "90") (name "unconnected-(CN3-A1-Pad7)") (class "Default")
      (node (ref "CN3") (pin "7") (pinfunction "A1_7") (pintype "passive"))
    )
    (net (code "91") (name "unconnected-(CN3-A2-Pad6)") (class "Default")
      (node (ref "CN3") (pin "6") (pinfunction "A2_6") (pintype "passive"))
    )
    (net (code "92") (name "unconnected-(CN3-GND-Pad9)") (class "Default")
      (node (ref "CN3") (pin "9") (pinfunction "GND_9") (pintype "passive"))
    )
    (net (code "93") (name "unconnected-(CN3-GND-Pad10)") (class "Default")
      (node (ref "CN3") (pin "10") (pinfunction "GND_10") (pintype "passive"))
    )
    (net (code "94") (name "unconnected-(CN3-GND-Pad13)") (class "Default")
      (node (ref "CN3") (pin "13") (pinfunction "GND_13") (pintype "passive"))
    )
    (net (code "95") (name "unconnected-(CN3-GND-Pad14)") (class "Default")
      (node (ref "CN3") (pin "14") (pinfunction "GND_14") (pintype "passive"))
    )
    (net (code "96") (name "unconnected-(CN3-NC-Pad17)") (class "Default")
      (node (ref "CN3") (pin "17") (pinfunction "NC_17") (pintype "passive"))
    )
    (net (code "97") (name "unconnected-(CN3-SCL-Pad4)") (class "Default")
      (node (ref "CN3") (pin "4") (pinfunction "SCL_4") (pintype "passive"))
    )
    (net (code "98") (name "unconnected-(CN3-SDA-Pad3)") (class "Default")
      (node (ref "CN3") (pin "3") (pinfunction "SDA_3") (pintype "passive"))
    )
    (net (code "99") (name "unconnected-(CN3-VDD-Pad16)") (class "Default")
      (node (ref "CN3") (pin "16") (pinfunction "VDD_16") (pintype "passive"))
    )
    (net (code "100") (name "unconnected-(CN4-A0-Pad8)") (class "Default")
      (node (ref "CN4") (pin "8") (pinfunction "A0_8") (pintype "passive"))
    )
    (net (code "101") (name "unconnected-(CN4-A1-Pad7)") (class "Default")
      (node (ref "CN4") (pin "7") (pinfunction "A1_7") (pintype "passive"))
    )
    (net (code "102") (name "unconnected-(CN4-A2-Pad6)") (class "Default")
      (node (ref "CN4") (pin "6") (pinfunction "A2_6") (pintype "passive"))
    )
    (net (code "103") (name "unconnected-(CN4-GND-Pad9)") (class "Default")
      (node (ref "CN4") (pin "9") (pinfunction "GND_9") (pintype "passive"))
    )
    (net (code "104") (name "unconnected-(CN4-GND-Pad10)") (class "Default")
      (node (ref "CN4") (pin "10") (pinfunction "GND_10") (pintype "passive"))
    )
    (net (code "105") (name "unconnected-(CN4-GND-Pad13)") (class "Default")
      (node (ref "CN4") (pin "13") (pinfunction "GND_13") (pintype "passive"))
    )
    (net (code "106") (name "unconnected-(CN4-GND-Pad14)") (class "Default")
      (node (ref "CN4") (pin "14") (pinfunction "GND_14") (pintype "passive"))
    )
    (net (code "107") (name "unconnected-(CN4-NC-Pad17)") (class "Default")
      (node (ref "CN4") (pin "17") (pinfunction "NC_17") (pintype "passive"))
    )
    (net (code "108") (name "unconnected-(CN4-PLUG-Pad5)") (class "Default")
      (node (ref "CN4") (pin "5") (pinfunction "PLUG_5") (pintype "bidirectional"))
    )
    (net (code "109") (name "unconnected-(CN4-SCL-Pad4)") (class "Default")
      (node (ref "CN4") (pin "4") (pinfunction "SCL_4") (pintype "passive"))
    )
    (net (code "110") (name "unconnected-(CN4-SDA-Pad3)") (class "Default")
      (node (ref "CN4") (pin "3") (pinfunction "SDA_3") (pintype "passive"))
    )
    (net (code "111") (name "unconnected-(CN4-TX-Pad11)") (class "Default")
      (node (ref "CN4") (pin "11") (pinfunction "TX_11") (pintype "bidirectional"))
    )
    (net (code "112") (name "unconnected-(U1-OTR-Pad28)") (class "Default")
      (node (ref "U1") (pin "28") (pinfunction "OTR_28") (pintype "passive"))
    )
  )
)
